# Programmable.net
KiCad netlist of a schematic drawn in EAGLE
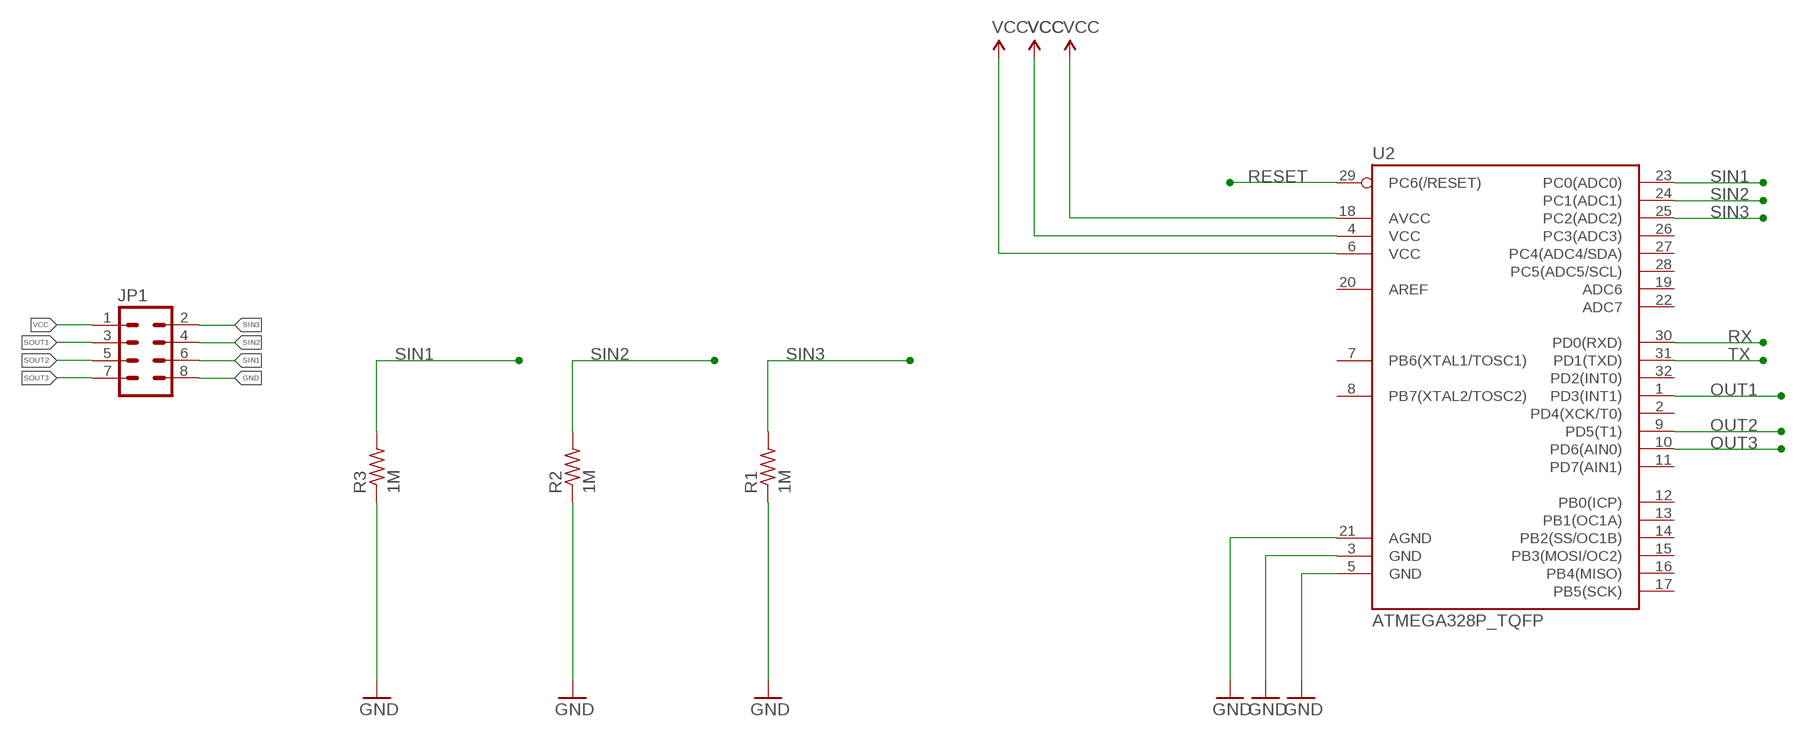
[diagram p0: schematic, sheet 1, part 1 of 2]
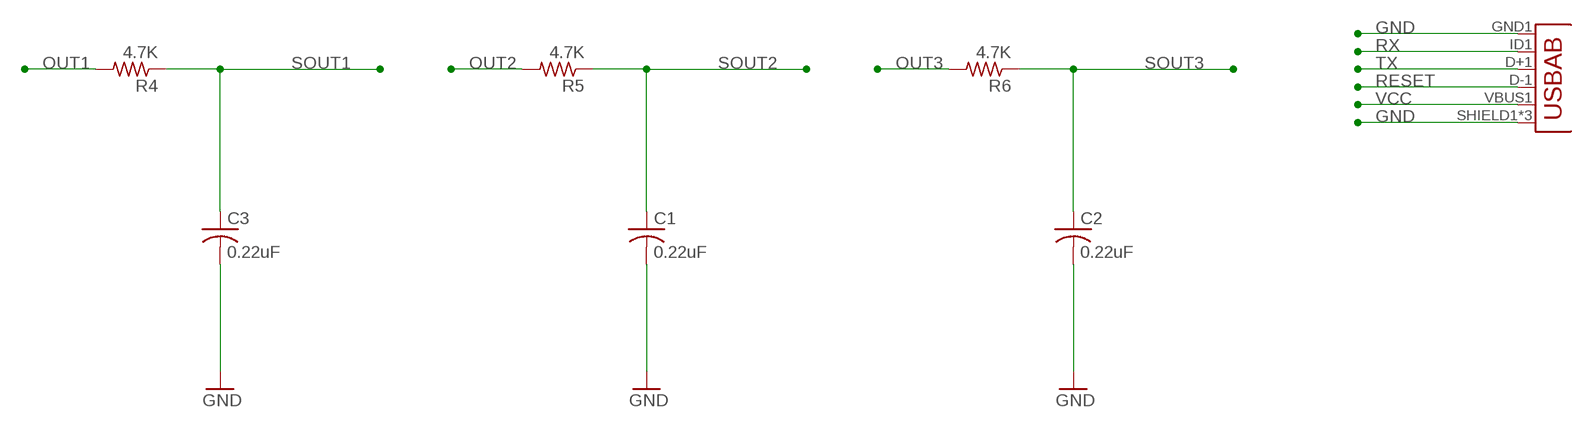
[diagram p1: schematic, sheet 1, part 2 of 2]

(export (version "E")
  (design (tool "Eeschema 10.0.6"))
  (components
    (comp (ref "C1")
      (value "0.22uF")
      (footprint "eagle-import:C0603")
      (libsource (lib "eagle-import") (part "C-USC0603"))
    )
    (comp (ref "C2")
      (value "0.22uF")
      (footprint "eagle-import:C0603")
      (libsource (lib "eagle-import") (part "C-USC0603"))
    )
    (comp (ref "C3")
      (value "0.22uF")
      (footprint "eagle-import:C0603")
      (libsource (lib "eagle-import") (part "C-USC0603"))
    )
    (comp (ref "JP1")
      (value "M04X2")
      (footprint "eagle-import:2X4")
      (libsource (lib "eagle-import") (part "M04X2"))
    )
    (comp (ref "JP5")
      (value "USB-ABCONN-11794")
      (footprint "eagle-import:USB-AB-MICRO-SMD_V03")
      (libsource (lib "eagle-import") (part "USB-ABCONN-11794"))
    )
    (comp (ref "R1")
      (value "1M")
      (footprint "eagle-import:R0603")
      (libsource (lib "eagle-import") (part "R-US_R0603"))
    )
    (comp (ref "R2")
      (value "1M")
      (footprint "eagle-import:R0603")
      (libsource (lib "eagle-import") (part "R-US_R0603"))
    )
    (comp (ref "R3")
      (value "1M")
      (footprint "eagle-import:R0603")
      (libsource (lib "eagle-import") (part "R-US_R0603"))
    )
    (comp (ref "R4")
      (value "4.7K")
      (footprint "eagle-import:R0603")
      (libsource (lib "eagle-import") (part "R-US_R0603"))
    )
    (comp (ref "R5")
      (value "4.7K")
      (footprint "eagle-import:R0603")
      (libsource (lib "eagle-import") (part "R-US_R0603"))
    )
    (comp (ref "R6")
      (value "4.7K")
      (footprint "eagle-import:R0603")
      (libsource (lib "eagle-import") (part "R-US_R0603"))
    )
    (comp (ref "U2")
      (value "ATMEGA328P_TQFP")
      (footprint "eagle-import:TQFP32-08")
      (libsource (lib "eagle-import") (part "ATMEGA328P_TQFP"))
    )
  )
  (nets
    (net (code "1") (name "/OUT1") (class "Default")
      (node (ref "R4") (pin "2") (pinfunction "2_2") (pintype "passive"))
      (node (ref "U2") (pin "1") (pinfunction "PD3(INT1)_1") (pintype "bidirectional"))
    )
    (net (code "2") (name "/OUT2") (class "Default")
      (node (ref "R5") (pin "2") (pinfunction "2_2") (pintype "passive"))
      (node (ref "U2") (pin "9") (pinfunction "PD5(T1)_9") (pintype "bidirectional"))
    )
    (net (code "3") (name "/OUT3") (class "Default")
      (node (ref "R6") (pin "2") (pinfunction "2_2") (pintype "passive"))
      (node (ref "U2") (pin "10") (pinfunction "PD6(AIN0)_10") (pintype "bidirectional"))
    )
    (net (code "4") (name "/RESET") (class "Default")
      (node (ref "JP5") (pin "D-1") (pinfunction "D-_D-1") (pintype "bidirectional"))
      (node (ref "U2") (pin "29") (pinfunction "PC6(/RESET)_29") (pintype "bidirectional"))
    )
    (net (code "5") (name "/RX") (class "Default")
      (node (ref "JP5") (pin "ID1") (pinfunction "USBID_ID1") (pintype "bidirectional"))
      (node (ref "U2") (pin "30") (pinfunction "PD0(RXD)_30") (pintype "bidirectional"))
    )
    (net (code "6") (name "/TX") (class "Default")
      (node (ref "JP5") (pin "D+1") (pinfunction "D+_D+1") (pintype "bidirectional"))
      (node (ref "U2") (pin "31") (pinfunction "PD1(TXD)_31") (pintype "bidirectional"))
    )
    (net (code "7") (name "GND") (class "Default")
      (node (ref "C1") (pin "2") (pinfunction "2_2") (pintype "passive"))
      (node (ref "C2") (pin "2") (pinfunction "2_2") (pintype "passive"))
      (node (ref "C3") (pin "2") (pinfunction "2_2") (pintype "passive"))
      (node (ref "JP1") (pin "8") (pinfunction "8_8") (pintype "passive"))
      (node (ref "JP5") (pin "GND1") (pinfunction "GND_GND1") (pintype "bidirectional"))
      (node (ref "JP5") (pin "SHIELD1") (pinfunction "SHIELD_SHIELD1") (pintype "bidirectional"))
      (node (ref "JP5") (pin "SHIELD2") (pinfunction "SHIELD_SHIELD2") (pintype "bidirectional"))
      (node (ref "JP5") (pin "SHIELD3") (pinfunction "SHIELD_SHIELD3") (pintype "bidirectional"))
      (node (ref "R1") (pin "1") (pinfunction "1_1") (pintype "passive"))
      (node (ref "R2") (pin "1") (pinfunction "1_1") (pintype "passive"))
      (node (ref "R3") (pin "1") (pinfunction "1_1") (pintype "passive"))
      (node (ref "U2") (pin "21") (pinfunction "AGND_21") (pintype "bidirectional"))
      (node (ref "U2") (pin "3") (pinfunction "GND_3") (pintype "bidirectional"))
      (node (ref "U2") (pin "5") (pinfunction "GND_5") (pintype "bidirectional"))
    )
    (net (code "8") (name "SIN1") (class "Default")
      (node (ref "JP1") (pin "6") (pinfunction "6_6") (pintype "passive"))
      (node (ref "R3") (pin "2") (pinfunction "2_2") (pintype "passive"))
      (node (ref "U2") (pin "23") (pinfunction "PC0(ADC0)_23") (pintype "bidirectional"))
    )
    (net (code "9") (name "SIN2") (class "Default")
      (node (ref "JP1") (pin "4") (pinfunction "4_4") (pintype "passive"))
      (node (ref "R2") (pin "2") (pinfunction "2_2") (pintype "passive"))
      (node (ref "U2") (pin "24") (pinfunction "PC1(ADC1)_24") (pintype "bidirectional"))
    )
    (net (code "10") (name "SIN3") (class "Default")
      (node (ref "JP1") (pin "2") (pinfunction "2_2") (pintype "passive"))
      (node (ref "R1") (pin "2") (pinfunction "2_2") (pintype "passive"))
      (node (ref "U2") (pin "25") (pinfunction "PC2(ADC2)_25") (pintype "bidirectional"))
    )
    (net (code "11") (name "SOUT1") (class "Default")
      (node (ref "C3") (pin "1") (pinfunction "1_1") (pintype "passive"))
      (node (ref "JP1") (pin "3") (pinfunction "3_3") (pintype "passive"))
      (node (ref "R4") (pin "1") (pinfunction "1_1") (pintype "passive"))
    )
    (net (code "12") (name "SOUT2") (class "Default")
      (node (ref "C1") (pin "1") (pinfunction "1_1") (pintype "passive"))
      (node (ref "JP1") (pin "5") (pinfunction "5_5") (pintype "passive"))
      (node (ref "R5") (pin "1") (pinfunction "1_1") (pintype "passive"))
    )
    (net (code "13") (name "SOUT3") (class "Default")
      (node (ref "C2") (pin "1") (pinfunction "1_1") (pintype "passive"))
      (node (ref "JP1") (pin "7") (pinfunction "7_7") (pintype "passive"))
      (node (ref "R6") (pin "1") (pinfunction "1_1") (pintype "passive"))
    )
    (net (code "14") (name "VCC") (class "Default")
      (node (ref "JP1") (pin "1") (pinfunction "1_1") (pintype "passive"))
      (node (ref "JP5") (pin "VBUS1") (pinfunction "VBUS_VBUS1") (pintype "bidirectional"))
      (node (ref "U2") (pin "18") (pinfunction "AVCC_18") (pintype "bidirectional"))
      (node (ref "U2") (pin "4") (pinfunction "VCC_4") (pintype "bidirectional"))
      (node (ref "U2") (pin "6") (pinfunction "VCC_6") (pintype "bidirectional"))
    )
    (net (code "15") (name "unconnected-(U2-ADC6-Pad19)") (class "Default")
      (node (ref "U2") (pin "19") (pinfunction "ADC6_19") (pintype "bidirectional"))
    )
    (net (code "16") (name "unconnected-(U2-ADC7-Pad22)") (class "Default")
      (node (ref "U2") (pin "22") (pinfunction "ADC7_22") (pintype "bidirectional"))
    )
    (net (code "17") (name "unconnected-(U2-AREF-Pad20)") (class "Default")
      (node (ref "U2") (pin "20") (pinfunction "AREF_20") (pintype "bidirectional"))
    )
    (net (code "18") (name "unconnected-(U2-PB0(ICP)-Pad12)") (class "Default")
      (node (ref "U2") (pin "12") (pinfunction "PB0(ICP)_12") (pintype "bidirectional"))
    )
    (net (code "19") (name "unconnected-(U2-PB1(OC1A)-Pad13)") (class "Default")
      (node (ref "U2") (pin "13") (pinfunction "PB1(OC1A)_13") (pintype "bidirectional"))
    )
    (net (code "20") (name "unconnected-(U2-PB2(SS{slash}OC1B)-Pad14)") (class "Default")
      (node (ref "U2") (pin "14") (pinfunction "PB2(SS/OC1B)_14") (pintype "bidirectional"))
    )
    (net (code "21") (name "unconnected-(U2-PB3(MOSI{slash}OC2)-Pad15)") (class "Default")
      (node (ref "U2") (pin "15") (pinfunction "PB3(MOSI/OC2)_15") (pintype "bidirectional"))
    )
    (net (code "22") (name "unconnected-(U2-PB4(MISO)-Pad16)") (class "Default")
      (node (ref "U2") (pin "16") (pinfunction "PB4(MISO)_16") (pintype "bidirectional"))
    )
    (net (code "23") (name "unconnected-(U2-PB5(SCK)-Pad17)") (class "Default")
      (node (ref "U2") (pin "17") (pinfunction "PB5(SCK)_17") (pintype "bidirectional"))
    )
    (net (code "24") (name "unconnected-(U2-PB6(XTAL1{slash}TOSC1)-Pad7)") (class "Default")
      (node (ref "U2") (pin "7") (pinfunction "PB6(XTAL1/TOSC1)_7") (pintype "bidirectional"))
    )
    (net (code "25") (name "unconnected-(U2-PB7(XTAL2{slash}TOSC2)-Pad8)") (class "Default")
      (node (ref "U2") (pin "8") (pinfunction "PB7(XTAL2/TOSC2)_8") (pintype "bidirectional"))
    )
    (net (code "26") (name "unconnected-(U2-PC3(ADC3)-Pad26)") (class "Default")
      (node (ref "U2") (pin "26") (pinfunction "PC3(ADC3)_26") (pintype "bidirectional"))
    )
    (net (code "27") (name "unconnected-(U2-PC4(ADC4{slash}SDA)-Pad27)") (class "Default")
      (node (ref "U2") (pin "27") (pinfunction "PC4(ADC4/SDA)_27") (pintype "bidirectional"))
    )
    (net (code "28") (name "unconnected-(U2-PC5(ADC5{slash}SCL)-Pad28)") (class "Default")
      (node (ref "U2") (pin "28") (pinfunction "PC5(ADC5/SCL)_28") (pintype "bidirectional"))
    )
    (net (code "29") (name "unconnected-(U2-PD2(INT0)-Pad32)") (class "Default")
      (node (ref "U2") (pin "32") (pinfunction "PD2(INT0)_32") (pintype "bidirectional"))
    )
    (net (code "30") (name "unconnected-(U2-PD4(XCK{slash}T0)-Pad2)") (class "Default")
      (node (ref "U2") (pin "2") (pinfunction "PD4(XCK/T0)_2") (pintype "bidirectional"))
    )
    (net (code "31") (name "unconnected-(U2-PD7(AIN1)-Pad11)") (class "Default")
      (node (ref "U2") (pin "11") (pinfunction "PD7(AIN1)_11") (pintype "bidirectional"))
    )
  )
)
